# 08_ADC_measure.net
KiCad netlist of a schematic drawn in Altium Designer
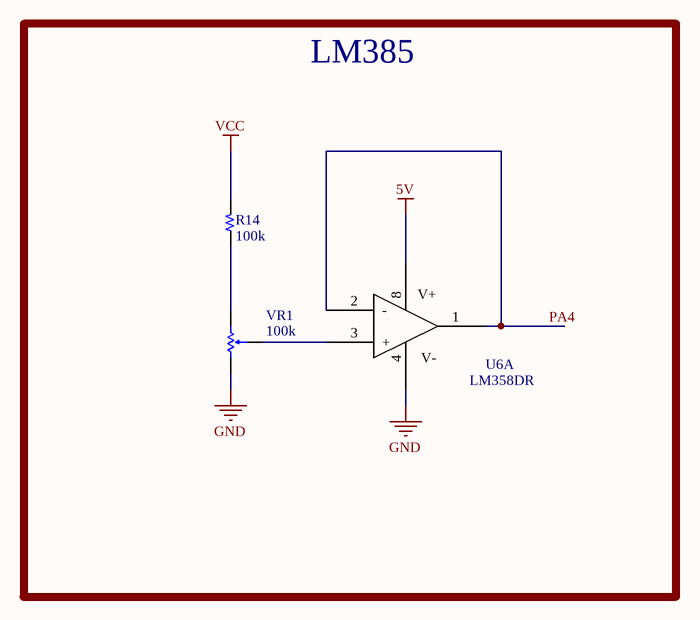
[diagram p0: 08_ADC_measure.SchDoc]

(export (version "E")
  (design (tool "Eeschema 10.0.6"))
  (components
    (comp (ref "R14")
      (value "100k")
      (footprint "R 0805")
      (description "Resistor")
      (libsource (lib "chipfc_libs") (part "Resistor"))
    )
    (comp (ref "U6")
      (value "LM358DR")
      (footprint "LM358DR")
      (description "Operational Amplifiers - Op Amps Dual Op Amp")
      (fields (field (name "MANUFACTURER") "Texas Instruments") (field (name "LCSC PART #") "C5423"))
      (libsource (lib "OPAMP") (part "LM358DR"))
    )
    (comp (ref "VR1")
      (value "100k")
      (footprint "R VAR E")
      (description "Resistor Variable")
      (libsource (lib "chipfc_libs") (part "Resistor Variable"))
    )
  )
  (nets
    (net (code "1") (name "/PA4") (class "Default")
      (node (ref "U6") (pin "1") (pinfunction "OUT_1_1") (pintype "passive"))
      (node (ref "U6") (pin "2") (pinfunction "-_2") (pintype "passive"))
    )
    (net (code "2") (name "5V") (class "Default")
      (node (ref "U6") (pin "8") (pinfunction "VCC_8") (pintype "passive"))
    )
    (net (code "3") (name "GND") (class "Default")
      (node (ref "U6") (pin "4") (pinfunction "GND_4") (pintype "passive"))
      (node (ref "VR1") (pin "3") (pinfunction "3_3") (pintype "passive"))
    )
    (net (code "4") (name "Net-(R14-Pad1)") (class "Default")
      (node (ref "R14") (pin "1") (pinfunction "1_1") (pintype "passive"))
      (node (ref "VR1") (pin "1") (pinfunction "1_1") (pintype "passive"))
    )
    (net (code "5") (name "Net-(U6A-+)") (class "Default")
      (node (ref "U6") (pin "3") (pinfunction "+_3") (pintype "passive"))
      (node (ref "VR1") (pin "2") (pinfunction "2_2") (pintype "passive"))
    )
    (net (code "6") (name "VCC") (class "Default")
      (node (ref "R14") (pin "2") (pinfunction "2_2") (pintype "passive"))
    )
  )
)
